# Teensy3_5.net
KiCad netlist of a schematic drawn in Altium Designer
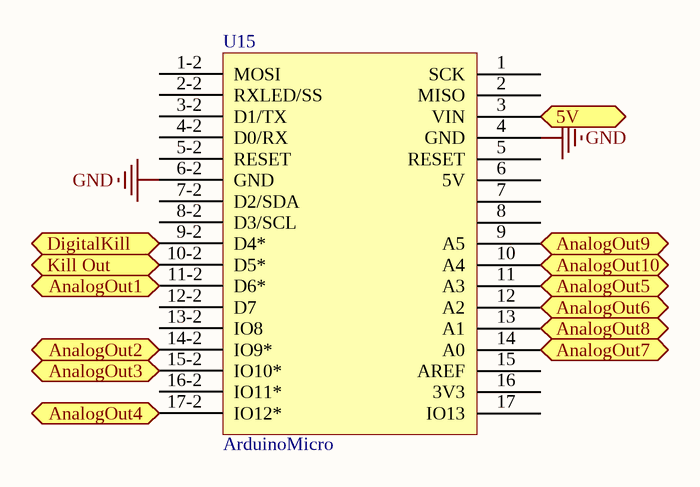
[diagram p0: Teensy3_5.SchDoc]

(export (version "E")
  (design (tool "Eeschema 10.0.6"))
  (components
    (comp (ref "U15")
      (value "ArduinoMicro")
      (footprint "ArduinoMicro")
      (libsource (lib "ArduinoMicro") (part "ArduinoMicro"))
    )
  )
  (nets
    (net (code "1") (name "/5V") (class "Default")
      (node (ref "U15") (pin "3") (pinfunction "VIN_3") (pintype "passive"))
    )
    (net (code "2") (name "/AnalogOut1") (class "Default")
      (node (ref "U15") (pin "11-2") (pinfunction "D6*_11-2") (pintype "passive"))
    )
    (net (code "3") (name "/AnalogOut2") (class "Default")
      (node (ref "U15") (pin "14-2") (pinfunction "IO9*_14-2") (pintype "passive"))
    )
    (net (code "4") (name "/AnalogOut3") (class "Default")
      (node (ref "U15") (pin "15-2") (pinfunction "IO10*_15-2") (pintype "passive"))
    )
    (net (code "5") (name "/AnalogOut4") (class "Default")
      (node (ref "U15") (pin "17-2") (pinfunction "IO12*_17-2") (pintype "passive"))
    )
    (net (code "6") (name "/AnalogOut5") (class "Default")
      (node (ref "U15") (pin "11") (pinfunction "A3_11") (pintype "passive"))
    )
    (net (code "7") (name "/AnalogOut6") (class "Default")
      (node (ref "U15") (pin "12") (pinfunction "A2_12") (pintype "passive"))
    )
    (net (code "8") (name "/AnalogOut7") (class "Default")
      (node (ref "U15") (pin "14") (pinfunction "A0_14") (pintype "passive"))
    )
    (net (code "9") (name "/AnalogOut8") (class "Default")
      (node (ref "U15") (pin "13") (pinfunction "A1_13") (pintype "passive"))
    )
    (net (code "10") (name "/AnalogOut9") (class "Default")
      (node (ref "U15") (pin "9") (pinfunction "A5_9") (pintype "passive"))
    )
    (net (code "11") (name "/AnalogOut10") (class "Default")
      (node (ref "U15") (pin "10") (pinfunction "A4_10") (pintype "passive"))
    )
    (net (code "12") (name "/DigitalKill") (class "Default")
      (node (ref "U15") (pin "9-2") (pinfunction "D4*_9-2") (pintype "passive"))
    )
    (net (code "13") (name "/Kill Out") (class "Default")
      (node (ref "U15") (pin "10-2") (pinfunction "D5*_10-2") (pintype "passive"))
    )
    (net (code "14") (name "GND") (class "Default")
      (node (ref "U15") (pin "4") (pinfunction "GND_4") (pintype "passive"))
      (node (ref "U15") (pin "6-2") (pinfunction "GND_6-2") (pintype "passive"))
    )
    (net (code "15") (name "unconnected-(U15-3V3-Pad16)") (class "Default")
      (node (ref "U15") (pin "16") (pinfunction "3V3_16") (pintype "passive"))
    )
    (net (code "16") (name "unconnected-(U15-5V-Pad6)") (class "Default")
      (node (ref "U15") (pin "6") (pinfunction "5V_6") (pintype "passive"))
    )
    (net (code "17") (name "unconnected-(U15-AREF-Pad15)") (class "Default")
      (node (ref "U15") (pin "15") (pinfunction "AREF_15") (pintype "passive"))
    )
    (net (code "18") (name "unconnected-(U15-D0{slash}RX-Pad4-2)") (class "Default")
      (node (ref "U15") (pin "4-2") (pinfunction "D0/RX_4-2") (pintype "passive"))
    )
    (net (code "19") (name "unconnected-(U15-D1{slash}TX-Pad3-2)") (class "Default")
      (node (ref "U15") (pin "3-2") (pinfunction "D1/TX_3-2") (pintype "passive"))
    )
    (net (code "20") (name "unconnected-(U15-D2{slash}SDA-Pad7-2)") (class "Default")
      (node (ref "U15") (pin "7-2") (pinfunction "D2/SDA_7-2") (pintype "passive"))
    )
    (net (code "21") (name "unconnected-(U15-D3{slash}SCL-Pad8-2)") (class "Default")
      (node (ref "U15") (pin "8-2") (pinfunction "D3/SCL_8-2") (pintype "passive"))
    )
    (net (code "22") (name "unconnected-(U15-D7-Pad12-2)") (class "Default")
      (node (ref "U15") (pin "12-2") (pinfunction "D7_12-2") (pintype "passive"))
    )
    (net (code "23") (name "unconnected-(U15-IO8-Pad13-2)") (class "Default")
      (node (ref "U15") (pin "13-2") (pinfunction "IO8_13-2") (pintype "passive"))
    )
    (net (code "24") (name "unconnected-(U15-IO11*-Pad16-2)") (class "Default")
      (node (ref "U15") (pin "16-2") (pinfunction "IO11*_16-2") (pintype "passive"))
    )
    (net (code "25") (name "unconnected-(U15-IO13-Pad17)") (class "Default")
      (node (ref "U15") (pin "17") (pinfunction "IO13_17") (pintype "passive"))
    )
    (net (code "26") (name "unconnected-(U15-MISO-Pad2)") (class "Default")
      (node (ref "U15") (pin "2") (pinfunction "MISO_2") (pintype "passive"))
    )
    (net (code "27") (name "unconnected-(U15-MOSI-Pad1-2)") (class "Default")
      (node (ref "U15") (pin "1-2") (pinfunction "MOSI_1-2") (pintype "passive"))
    )
    (net (code "28") (name "unconnected-(U15-Pad7)") (class "Default")
      (node (ref "U15") (pin "7") (pintype "passive"))
    )
    (net (code "29") (name "unconnected-(U15-Pad8)") (class "Default")
      (node (ref "U15") (pin "8") (pintype "passive"))
    )
    (net (code "30") (name "unconnected-(U15-RESET-Pad5)") (class "Default")
      (node (ref "U15") (pin "5") (pinfunction "RESET_5") (pintype "passive"))
    )
    (net (code "31") (name "unconnected-(U15-RESET-Pad5-2)") (class "Default")
      (node (ref "U15") (pin "5-2") (pinfunction "RESET_5-2") (pintype "passive"))
    )
    (net (code "32") (name "unconnected-(U15-RXLED{slash}SS-Pad2-2)") (class "Default")
      (node (ref "U15") (pin "2-2") (pinfunction "RXLED/SS_2-2") (pintype "passive"))
    )
    (net (code "33") (name "unconnected-(U15-SCK-Pad1)") (class "Default")
      (node (ref "U15") (pin "1") (pinfunction "SCK_1") (pintype "passive"))
    )
  )
)
